# ProPrj_TCC_PCB.net
KiCad netlist of a schematic drawn in EasyEDA Pro
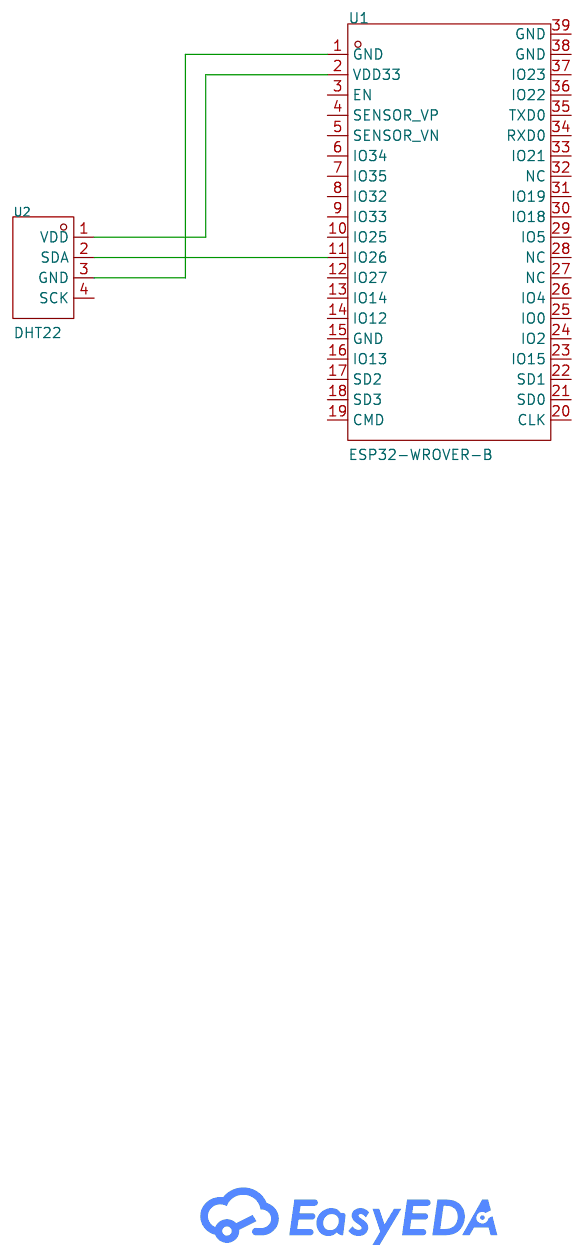
[diagram p0: schematic sheet]

(export (version "E")
  (design (tool "Eeschema 10.0.6"))
  (components
    (comp (ref "U1")
      (value "ESP32-WROVER-B")
      (footprint "easyedapro:WIFIM-SMD_39P-L31.4-W18.0-P1.27")
      (fields (field (name "Manufacturer") "ESPRESSIF(乐鑫)"))
      (libsource (lib "easyedapro") (part "ESP32-WROVER-B"))
    )
    (comp (ref "U2")
      (value "DHT22")
      (footprint "easyedapro:SENSOR-TH_HAIGU_DHT22")
      (fields (field (name "Manufacturer") "HAIGU(广州海谷)"))
      (libsource (lib "easyedapro") (part "DHT22"))
    )
  )
  (nets
    (net (code "1") (name "Net-(U1-IO26)") (class "Default")
      (node (ref "U1") (pin "11") (pinfunction "IO26_11") (pintype "unspecified"))
      (node (ref "U2") (pin "2") (pinfunction "SDA_2") (pintype "input"))
    )
    (net (code "2") (name "Net-(U1-VDD33)") (class "Default")
      (node (ref "U1") (pin "2") (pinfunction "VDD33_2") (pintype "unspecified"))
      (node (ref "U2") (pin "1") (pinfunction "VDD_1") (pintype "input"))
    )
    (net (code "3") (name "Net-(U2-GND)") (class "Default")
      (node (ref "U1") (pin "1") (pinfunction "GND_1") (pintype "unspecified"))
      (node (ref "U2") (pin "3") (pinfunction "GND_3") (pintype "input"))
    )
    (net (code "4") (name "unconnected-(U1-CLK-Pad20)") (class "Default")
      (node (ref "U1") (pin "20") (pinfunction "CLK_20") (pintype "unspecified"))
    )
    (net (code "5") (name "unconnected-(U1-CMD-Pad19)") (class "Default")
      (node (ref "U1") (pin "19") (pinfunction "CMD_19") (pintype "unspecified"))
    )
    (net (code "6") (name "unconnected-(U1-EN-Pad3)") (class "Default")
      (node (ref "U1") (pin "3") (pinfunction "EN_3") (pintype "unspecified"))
    )
    (net (code "7") (name "unconnected-(U1-GND-Pad15)") (class "Default")
      (node (ref "U1") (pin "15") (pinfunction "GND_15") (pintype "unspecified"))
    )
    (net (code "8") (name "unconnected-(U1-GND-Pad38)") (class "Default")
      (node (ref "U1") (pin "38") (pinfunction "GND_38") (pintype "unspecified"))
    )
    (net (code "9") (name "unconnected-(U1-GND-Pad39)") (class "Default")
      (node (ref "U1") (pin "39") (pinfunction "GND_39") (pintype "unspecified"))
    )
    (net (code "10") (name "unconnected-(U1-IO0-Pad25)") (class "Default")
      (node (ref "U1") (pin "25") (pinfunction "IO0_25") (pintype "unspecified"))
    )
    (net (code "11") (name "unconnected-(U1-IO2-Pad24)") (class "Default")
      (node (ref "U1") (pin "24") (pinfunction "IO2_24") (pintype "unspecified"))
    )
    (net (code "12") (name "unconnected-(U1-IO4-Pad26)") (class "Default")
      (node (ref "U1") (pin "26") (pinfunction "IO4_26") (pintype "unspecified"))
    )
    (net (code "13") (name "unconnected-(U1-IO5-Pad29)") (class "Default")
      (node (ref "U1") (pin "29") (pinfunction "IO5_29") (pintype "unspecified"))
    )
    (net (code "14") (name "unconnected-(U1-IO12-Pad14)") (class "Default")
      (node (ref "U1") (pin "14") (pinfunction "IO12_14") (pintype "unspecified"))
    )
    (net (code "15") (name "unconnected-(U1-IO13-Pad16)") (class "Default")
      (node (ref "U1") (pin "16") (pinfunction "IO13_16") (pintype "unspecified"))
    )
    (net (code "16") (name "unconnected-(U1-IO14-Pad13)") (class "Default")
      (node (ref "U1") (pin "13") (pinfunction "IO14_13") (pintype "unspecified"))
    )
    (net (code "17") (name "unconnected-(U1-IO15-Pad23)") (class "Default")
      (node (ref "U1") (pin "23") (pinfunction "IO15_23") (pintype "unspecified"))
    )
    (net (code "18") (name "unconnected-(U1-IO18-Pad30)") (class "Default")
      (node (ref "U1") (pin "30") (pinfunction "IO18_30") (pintype "unspecified"))
    )
    (net (code "19") (name "unconnected-(U1-IO19-Pad31)") (class "Default")
      (node (ref "U1") (pin "31") (pinfunction "IO19_31") (pintype "unspecified"))
    )
    (net (code "20") (name "unconnected-(U1-IO21-Pad33)") (class "Default")
      (node (ref "U1") (pin "33") (pinfunction "IO21_33") (pintype "unspecified"))
    )
    (net (code "21") (name "unconnected-(U1-IO22-Pad36)") (class "Default")
      (node (ref "U1") (pin "36") (pinfunction "IO22_36") (pintype "unspecified"))
    )
    (net (code "22") (name "unconnected-(U1-IO23-Pad37)") (class "Default")
      (node (ref "U1") (pin "37") (pinfunction "IO23_37") (pintype "unspecified"))
    )
    (net (code "23") (name "unconnected-(U1-IO25-Pad10)") (class "Default")
      (node (ref "U1") (pin "10") (pinfunction "IO25_10") (pintype "unspecified"))
    )
    (net (code "24") (name "unconnected-(U1-IO27-Pad12)") (class "Default")
      (node (ref "U1") (pin "12") (pinfunction "IO27_12") (pintype "unspecified"))
    )
    (net (code "25") (name "unconnected-(U1-IO32-Pad8)") (class "Default")
      (node (ref "U1") (pin "8") (pinfunction "IO32_8") (pintype "unspecified"))
    )
    (net (code "26") (name "unconnected-(U1-IO33-Pad9)") (class "Default")
      (node (ref "U1") (pin "9") (pinfunction "IO33_9") (pintype "unspecified"))
    )
    (net (code "27") (name "unconnected-(U1-IO34-Pad6)") (class "Default")
      (node (ref "U1") (pin "6") (pinfunction "IO34_6") (pintype "unspecified"))
    )
    (net (code "28") (name "unconnected-(U1-IO35-Pad7)") (class "Default")
      (node (ref "U1") (pin "7") (pinfunction "IO35_7") (pintype "unspecified"))
    )
    (net (code "29") (name "unconnected-(U1-NC-Pad27)") (class "Default")
      (node (ref "U1") (pin "27") (pinfunction "NC_27") (pintype "unspecified"))
    )
    (net (code "30") (name "unconnected-(U1-NC-Pad28)") (class "Default")
      (node (ref "U1") (pin "28") (pinfunction "NC_28") (pintype "unspecified"))
    )
    (net (code "31") (name "unconnected-(U1-NC-Pad32)") (class "Default")
      (node (ref "U1") (pin "32") (pinfunction "NC_32") (pintype "unspecified"))
    )
    (net (code "32") (name "unconnected-(U1-RXD0-Pad34)") (class "Default")
      (node (ref "U1") (pin "34") (pinfunction "RXD0_34") (pintype "unspecified"))
    )
    (net (code "33") (name "unconnected-(U1-SD0-Pad21)") (class "Default")
      (node (ref "U1") (pin "21") (pinfunction "SD0_21") (pintype "unspecified"))
    )
    (net (code "34") (name "unconnected-(U1-SD1-Pad22)") (class "Default")
      (node (ref "U1") (pin "22") (pinfunction "SD1_22") (pintype "unspecified"))
    )
    (net (code "35") (name "unconnected-(U1-SD2-Pad17)") (class "Default")
      (node (ref "U1") (pin "17") (pinfunction "SD2_17") (pintype "unspecified"))
    )
    (net (code "36") (name "unconnected-(U1-SD3-Pad18)") (class "Default")
      (node (ref "U1") (pin "18") (pinfunction "SD3_18") (pintype "unspecified"))
    )
    (net (code "37") (name "unconnected-(U1-SENSOR_VN-Pad5)") (class "Default")
      (node (ref "U1") (pin "5") (pinfunction "SENSOR_VN_5") (pintype "unspecified"))
    )
    (net (code "38") (name "unconnected-(U1-SENSOR_VP-Pad4)") (class "Default")
      (node (ref "U1") (pin "4") (pinfunction "SENSOR_VP_4") (pintype "unspecified"))
    )
    (net (code "39") (name "unconnected-(U1-TXD0-Pad35)") (class "Default")
      (node (ref "U1") (pin "35") (pinfunction "TXD0_35") (pintype "unspecified"))
    )
    (net (code "40") (name "unconnected-(U2-SCK-Pad4)") (class "Default")
      (node (ref "U2") (pin "4") (pinfunction "SCK_4") (pintype "input"))
    )
  )
)
